# AIO.net
KiCad netlist of a schematic drawn in EAGLE
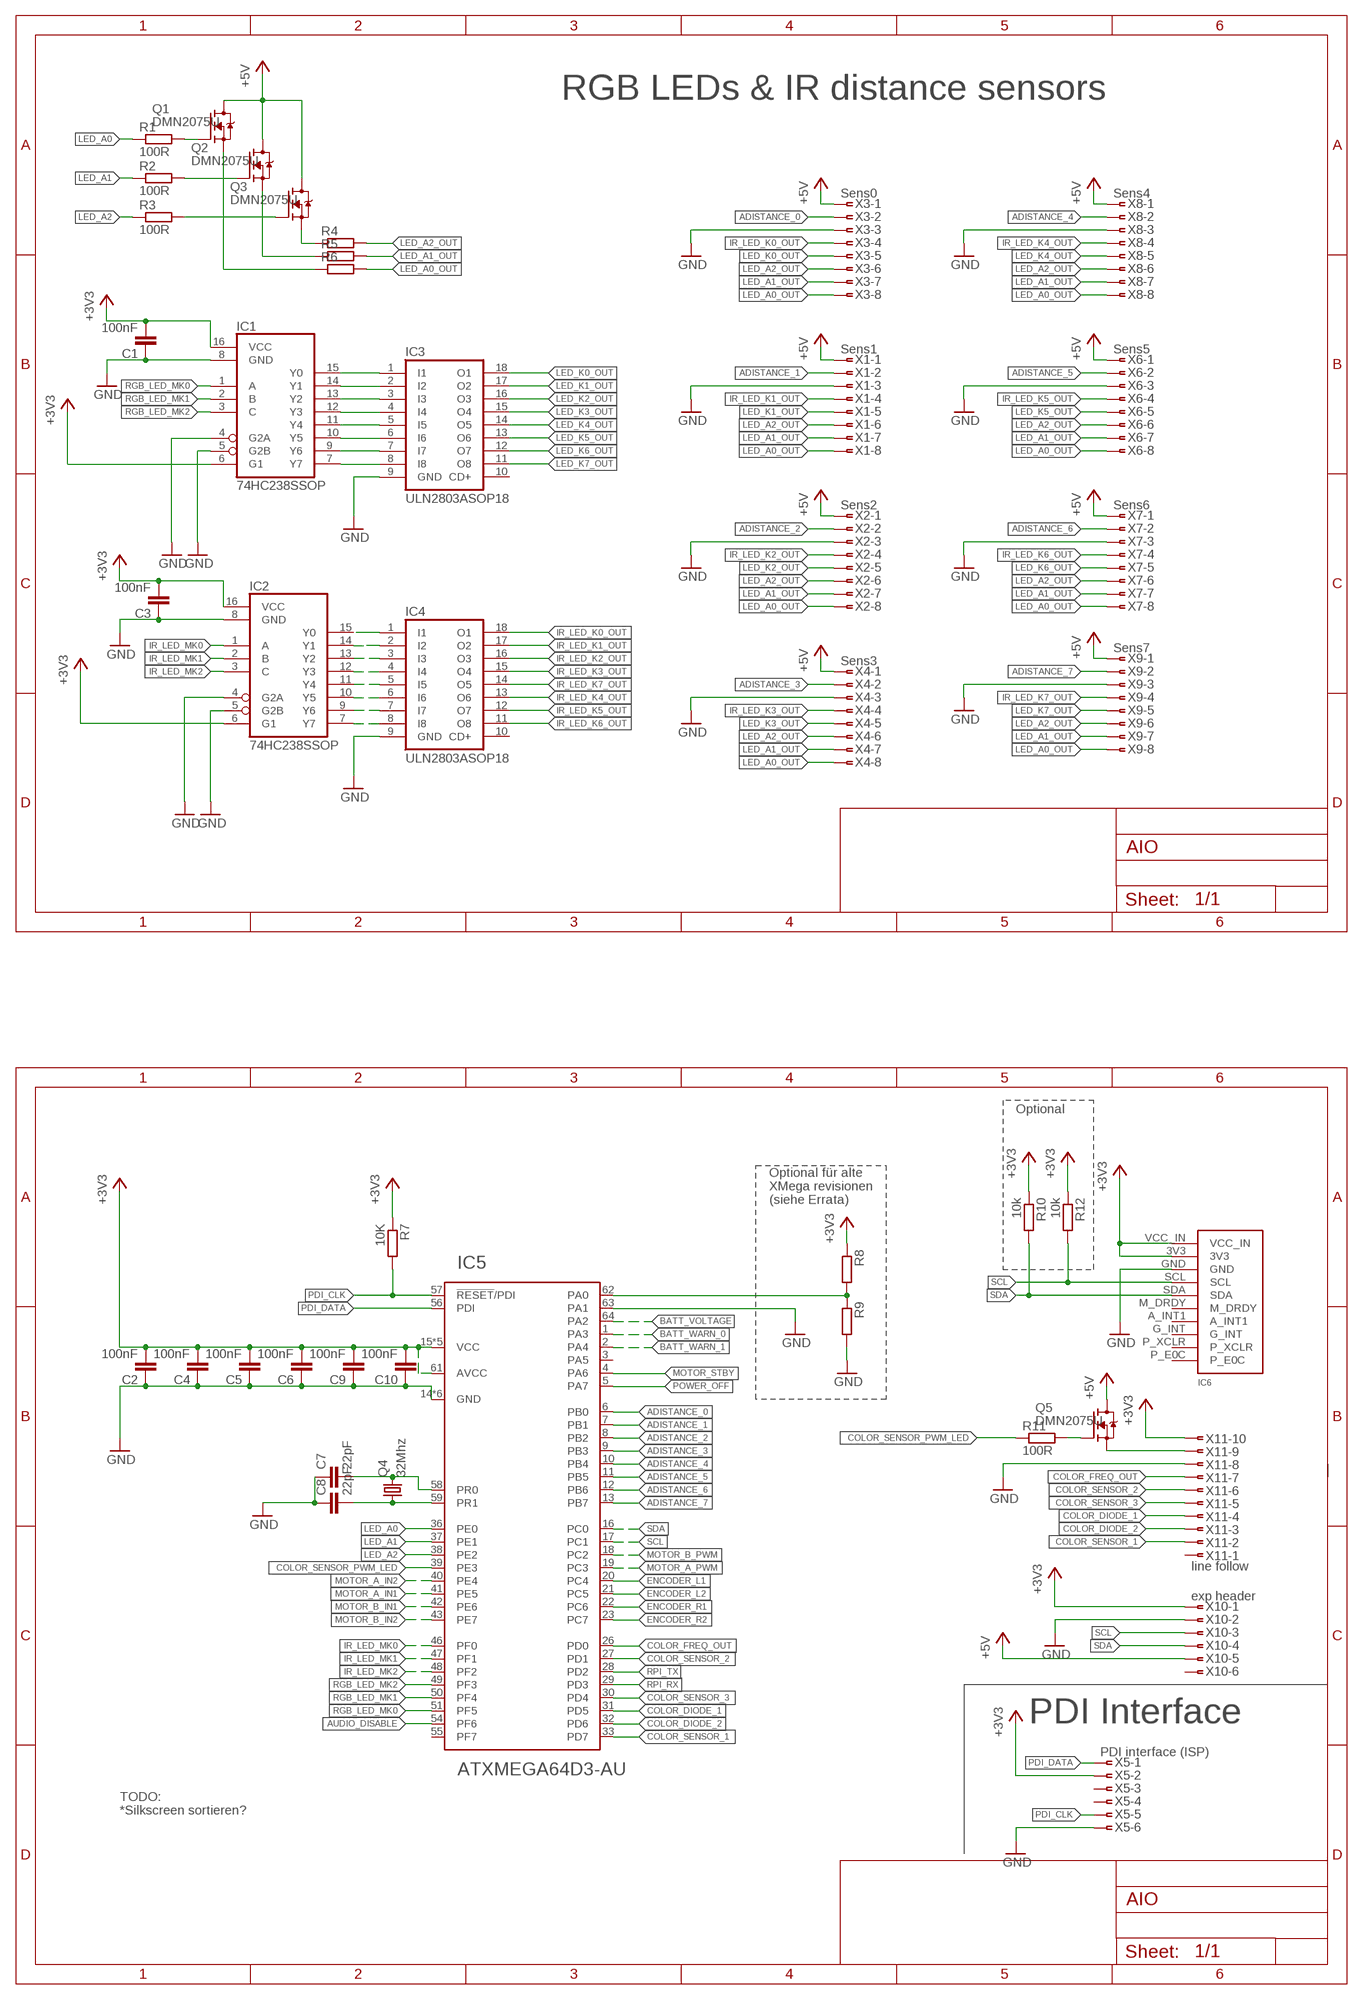
[diagram p0: schematic, sheet 1, part 1 of 2]
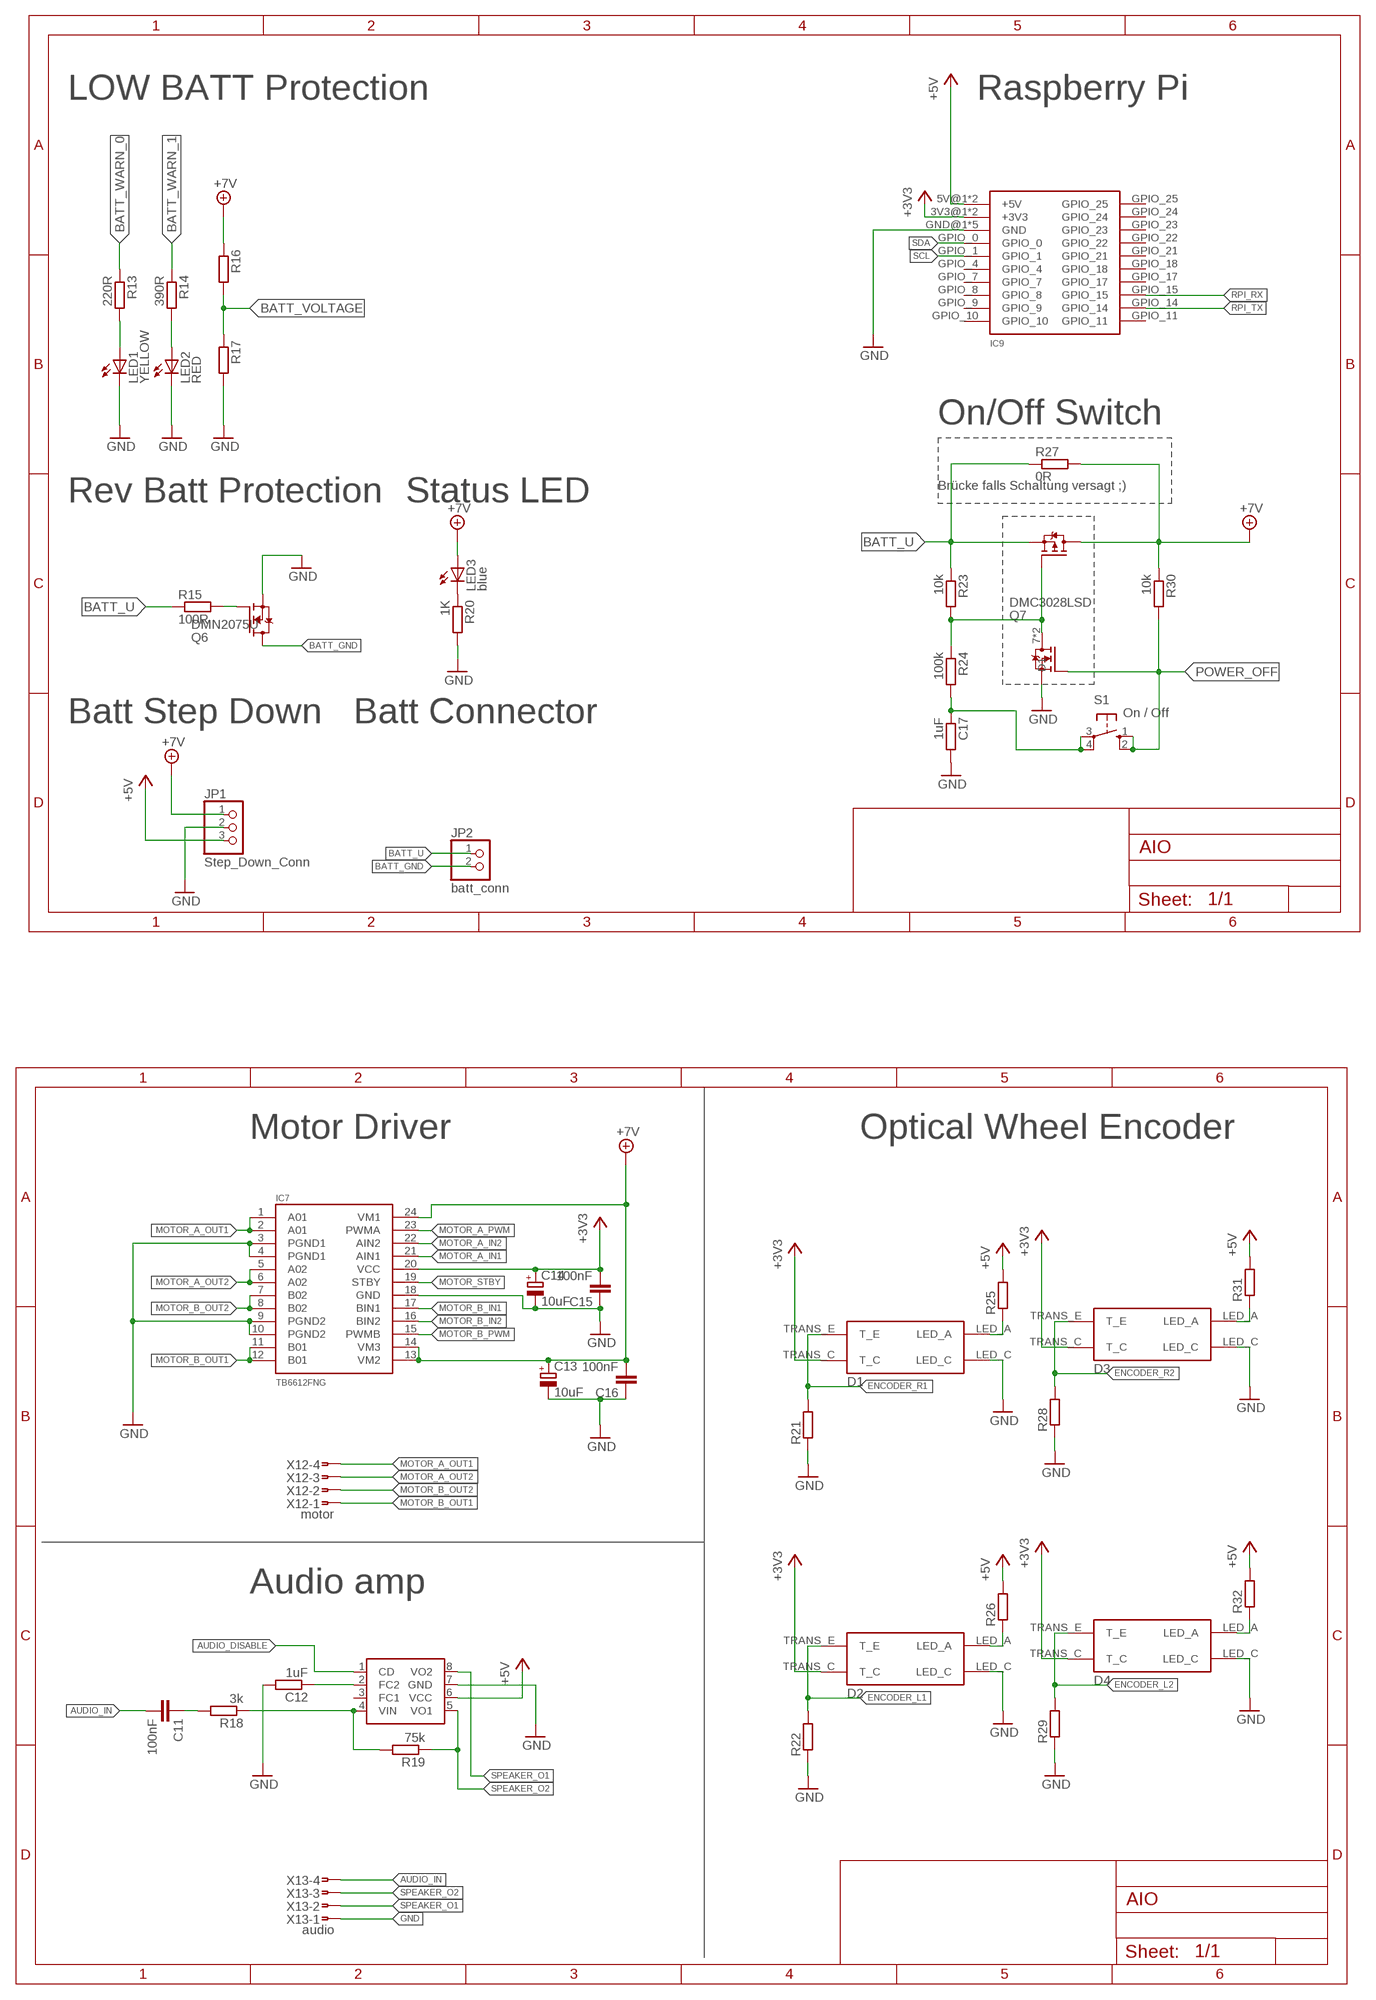
[diagram p1: schematic, sheet 1, part 2 of 2]

(export (version "E")
  (design (tool "Eeschema 10.0.6"))
  (components
    (comp (ref "C1")
      (value "100nF")
      (footprint "eagle-import:C0603")
      (libsource (lib "eagle-import") (part "C-EUC0603"))
    )
    (comp (ref "C2")
      (value "100nF")
      (footprint "eagle-import:C0603")
      (libsource (lib "eagle-import") (part "C-EUC0603"))
    )
    (comp (ref "C3")
      (value "100nF")
      (footprint "eagle-import:C0603")
      (libsource (lib "eagle-import") (part "C-EUC0603"))
    )
    (comp (ref "C4")
      (value "100nF")
      (footprint "eagle-import:C0603")
      (libsource (lib "eagle-import") (part "C-EUC0603"))
    )
    (comp (ref "C5")
      (value "100nF")
      (footprint "eagle-import:C0603")
      (libsource (lib "eagle-import") (part "C-EUC0603"))
    )
    (comp (ref "C6")
      (value "100nF")
      (footprint "eagle-import:C0603")
      (libsource (lib "eagle-import") (part "C-EUC0603"))
    )
    (comp (ref "C7")
      (value "22pF")
      (footprint "eagle-import:C0603")
      (libsource (lib "eagle-import") (part "C-EUC0603"))
    )
    (comp (ref "C8")
      (value "22pF")
      (footprint "eagle-import:C0603")
      (libsource (lib "eagle-import") (part "C-EUC0603"))
    )
    (comp (ref "C9")
      (value "100nF")
      (footprint "eagle-import:C0603")
      (libsource (lib "eagle-import") (part "C-EUC0603"))
    )
    (comp (ref "C10")
      (value "100nF")
      (footprint "eagle-import:C0603")
      (libsource (lib "eagle-import") (part "C-EUC0603"))
    )
    (comp (ref "C11")
      (value "100nF")
      (footprint "eagle-import:C0603")
      (libsource (lib "eagle-import") (part "C-EUC0603"))
    )
    (comp (ref "C12")
      (value "1uF")
      (footprint "eagle-import:M0805")
      (libsource (lib "eagle-import") (part "resistor_R-EU_M0805"))
    )
    (comp (ref "C13")
      (value "10uF")
      (footprint "eagle-import:E2-5")
      (libsource (lib "eagle-import") (part "CPOL-EUE2-5"))
    )
    (comp (ref "C14")
      (value "10uF")
      (footprint "eagle-import:E2-5")
      (libsource (lib "eagle-import") (part "CPOL-EUE2-5"))
    )
    (comp (ref "C15")
      (value "100nF")
      (footprint "eagle-import:C0603")
      (libsource (lib "eagle-import") (part "C-EUC0603"))
    )
    (comp (ref "C16")
      (value "100nF")
      (footprint "eagle-import:C0603")
      (libsource (lib "eagle-import") (part "C-EUC0603"))
    )
    (comp (ref "C17")
      (value "1uF")
      (footprint "eagle-import:M0805")
      (libsource (lib "eagle-import") (part "resistor_R-EU_M0805"))
    )
    (comp (ref "D1")
      (value "CNY70")
      (footprint "eagle-import:CNY70")
      (libsource (lib "eagle-import") (part "CNY70"))
    )
    (comp (ref "D2")
      (value "CNY70")
      (footprint "eagle-import:CNY70")
      (libsource (lib "eagle-import") (part "CNY70"))
    )
    (comp (ref "D3")
      (value "CNY70")
      (footprint "eagle-import:CNY70")
      (libsource (lib "eagle-import") (part "CNY70"))
    )
    (comp (ref "D4")
      (value "CNY70")
      (footprint "eagle-import:CNY70")
      (libsource (lib "eagle-import") (part "CNY70"))
    )
    (comp (ref "IC1")
      (value "74HC238SSOP")
      (footprint "eagle-import:SSOP16")
      (libsource (lib "eagle-import") (part "74HC238SSOP"))
    )
    (comp (ref "IC2")
      (value "74HC238SSOP")
      (footprint "eagle-import:SSOP16")
      (libsource (lib "eagle-import") (part "74HC238SSOP"))
    )
    (comp (ref "IC3")
      (value "ULN2803ASOP18")
      (footprint "eagle-import:SOP18")
      (libsource (lib "eagle-import") (part "ULN2803ASOP18"))
    )
    (comp (ref "IC4")
      (value "ULN2803ASOP18")
      (footprint "eagle-import:SOP18")
      (libsource (lib "eagle-import") (part "ULN2803ASOP18"))
    )
    (comp (ref "IC5")
      (value "ATXMEGA64D3-AU")
      (footprint "eagle-import:TQFP-64A-64")
      (libsource (lib "eagle-import") (part "ATXMEGA64D3-AU"))
    )
    (comp (ref "IC6")
      (value "GY-81")
      (footprint "eagle-import:GY-81")
      (libsource (lib "eagle-import") (part "GY-81"))
    )
    (comp (ref "IC7")
      (value "TB6612FNG")
      (footprint "eagle-import:SSOP24")
      (libsource (lib "eagle-import") (part "TB6621FNG"))
    )
    (comp (ref "IC8")
      (value "TS34119SMD")
      (footprint "eagle-import:SO08")
      (libsource (lib "eagle-import") (part "TS34119SMD"))
    )
    (comp (ref "IC9")
      (value "RASPBERRY-PI")
      (footprint "eagle-import:RASPERRRY-PI")
      (libsource (lib "eagle-import") (part "RASPBERRY-PI"))
    )
    (comp (ref "JP1")
      (value "Step_Down_Conn")
      (footprint "eagle-import:1X03")
      (libsource (lib "eagle-import") (part "PINHD-1X3"))
    )
    (comp (ref "JP2")
      (value "batt_conn")
      (footprint "eagle-import:1X02")
      (libsource (lib "eagle-import") (part "PINHD-1X2"))
    )
    (comp (ref "LED1")
      (value "YELLOW")
      (footprint "eagle-import:CHIPLED_0603")
      (libsource (lib "eagle-import") (part "LEDCHIPLED_0603"))
    )
    (comp (ref "LED2")
      (value "RED")
      (footprint "eagle-import:CHIPLED_0603")
      (libsource (lib "eagle-import") (part "LEDCHIPLED_0603"))
    )
    (comp (ref "LED3")
      (value "blue")
      (footprint "eagle-import:CHIPLED_0603")
      (libsource (lib "eagle-import") (part "LEDCHIPLED_0603"))
    )
    (comp (ref "Q1")
      (value "DMN2075U")
      (footprint "eagle-import:SOT95P240X112-3N")
      (libsource (lib "eagle-import") (part "DMN2075U"))
    )
    (comp (ref "Q2")
      (value "DMN2075U")
      (footprint "eagle-import:SOT95P240X112-3N")
      (libsource (lib "eagle-import") (part "DMN2075U"))
    )
    (comp (ref "Q3")
      (value "DMN2075U")
      (footprint "eagle-import:SOT95P240X112-3N")
      (libsource (lib "eagle-import") (part "DMN2075U"))
    )
    (comp (ref "Q4")
      (value "32Mhz")
      (footprint "eagle-import:HC18U-V")
      (libsource (lib "eagle-import") (part "CRYSTALHC18U-V"))
    )
    (comp (ref "Q5")
      (value "DMN2075U")
      (footprint "eagle-import:SOT95P240X112-3N")
      (libsource (lib "eagle-import") (part "DMN2075U"))
    )
    (comp (ref "Q6")
      (value "DMN2075U")
      (footprint "eagle-import:SOT95P240X112-3N")
      (libsource (lib "eagle-import") (part "DMN2075U"))
    )
    (comp (ref "Q7")
      (value "DMC3028LSD")
      (footprint "eagle-import:SO08")
      (libsource (lib "eagle-import") (part "DMC3028LSD"))
    )
    (comp (ref "R1")
      (value "100R")
      (footprint "eagle-import:R0603")
      (libsource (lib "eagle-import") (part "R-EU_R0603"))
    )
    (comp (ref "R2")
      (value "100R")
      (footprint "eagle-import:R0603")
      (libsource (lib "eagle-import") (part "R-EU_R0603"))
    )
    (comp (ref "R3")
      (value "100R")
      (footprint "eagle-import:R0603")
      (libsource (lib "eagle-import") (part "R-EU_R0603"))
    )
    (comp (ref "R4")
      (value "R-EU_M0805")
      (footprint "eagle-import:M0805")
      (libsource (lib "eagle-import") (part "resistor_R-EU_M0805"))
    )
    (comp (ref "R5")
      (value "R-EU_M0805")
      (footprint "eagle-import:M0805")
      (libsource (lib "eagle-import") (part "resistor_R-EU_M0805"))
    )
    (comp (ref "R6")
      (value "R-EU_M0805")
      (footprint "eagle-import:M0805")
      (libsource (lib "eagle-import") (part "resistor_R-EU_M0805"))
    )
    (comp (ref "R7")
      (value "10K")
      (footprint "eagle-import:M0805")
      (libsource (lib "eagle-import") (part "resistor_R-EU_M0805"))
    )
    (comp (ref "R8")
      (value "R-EU_M0805")
      (footprint "eagle-import:M0805")
      (libsource (lib "eagle-import") (part "R-EU_M0805"))
    )
    (comp (ref "R9")
      (value "R-EU_M0805")
      (footprint "eagle-import:M0805")
      (libsource (lib "eagle-import") (part "R-EU_M0805"))
    )
    (comp (ref "R10")
      (value "10k")
      (footprint "eagle-import:M0805")
      (libsource (lib "eagle-import") (part "resistor_R-EU_M0805"))
    )
    (comp (ref "R11")
      (value "100R")
      (footprint "eagle-import:R0603")
      (libsource (lib "eagle-import") (part "R-EU_R0603"))
    )
    (comp (ref "R12")
      (value "10k")
      (footprint "eagle-import:M0805")
      (libsource (lib "eagle-import") (part "resistor_R-EU_M0805"))
    )
    (comp (ref "R13")
      (value "220R")
      (footprint "eagle-import:M0805")
      (libsource (lib "eagle-import") (part "resistor_R-EU_M0805"))
    )
    (comp (ref "R14")
      (value "390R")
      (footprint "eagle-import:M0805")
      (libsource (lib "eagle-import") (part "resistor_R-EU_M0805"))
    )
    (comp (ref "R15")
      (value "100R")
      (footprint "eagle-import:R0603")
      (libsource (lib "eagle-import") (part "R-EU_R0603"))
    )
    (comp (ref "R16")
      (value "R-EU_M0805")
      (footprint "eagle-import:M0805")
      (libsource (lib "eagle-import") (part "resistor_R-EU_M0805"))
    )
    (comp (ref "R17")
      (value "R-EU_M0805")
      (footprint "eagle-import:M0805")
      (libsource (lib "eagle-import") (part "resistor_R-EU_M0805"))
    )
    (comp (ref "R18")
      (value "3k")
      (footprint "eagle-import:M0805")
      (libsource (lib "eagle-import") (part "resistor_R-EU_M0805"))
    )
    (comp (ref "R19")
      (value "75k")
      (footprint "eagle-import:M0805")
      (libsource (lib "eagle-import") (part "resistor_R-EU_M0805"))
    )
    (comp (ref "R20")
      (value "1K")
      (footprint "eagle-import:M0805")
      (libsource (lib "eagle-import") (part "resistor_R-EU_M0805"))
    )
    (comp (ref "R21")
      (value "R-EU_M0805")
      (footprint "eagle-import:M0805")
      (libsource (lib "eagle-import") (part "resistor_R-EU_M0805"))
    )
    (comp (ref "R22")
      (value "R-EU_M0805")
      (footprint "eagle-import:M0805")
      (libsource (lib "eagle-import") (part "resistor_R-EU_M0805"))
    )
    (comp (ref "R23")
      (value "10k")
      (footprint "eagle-import:M0805")
      (libsource (lib "eagle-import") (part "resistor_R-EU_M0805"))
    )
    (comp (ref "R24")
      (value "100k")
      (footprint "eagle-import:M0805")
      (libsource (lib "eagle-import") (part "resistor_R-EU_M0805"))
    )
    (comp (ref "R25")
      (value "R-EU_M0805")
      (footprint "eagle-import:M0805")
      (libsource (lib "eagle-import") (part "resistor_R-EU_M0805"))
    )
    (comp (ref "R26")
      (value "R-EU_M0805")
      (footprint "eagle-import:M0805")
      (libsource (lib "eagle-import") (part "resistor_R-EU_M0805"))
    )
    (comp (ref "R27")
      (value "0R")
      (footprint "eagle-import:M0805")
      (libsource (lib "eagle-import") (part "resistor_R-EU_M0805"))
    )
    (comp (ref "R28")
      (value "R-EU_M0805")
      (footprint "eagle-import:M0805")
      (libsource (lib "eagle-import") (part "resistor_R-EU_M0805"))
    )
    (comp (ref "R29")
      (value "R-EU_M0805")
      (footprint "eagle-import:M0805")
      (libsource (lib "eagle-import") (part "resistor_R-EU_M0805"))
    )
    (comp (ref "R30")
      (value "10k")
      (footprint "eagle-import:M0805")
      (libsource (lib "eagle-import") (part "resistor_R-EU_M0805"))
    )
    (comp (ref "R31")
      (value "R-EU_M0805")
      (footprint "eagle-import:M0805")
      (libsource (lib "eagle-import") (part "resistor_R-EU_M0805"))
    )
    (comp (ref "R32")
      (value "R-EU_M0805")
      (footprint "eagle-import:M0805")
      (libsource (lib "eagle-import") (part "resistor_R-EU_M0805"))
    )
    (comp (ref "S1")
      (value "On / Off")
      (footprint "eagle-import:B3F-10XX")
      (fields (field (name "MPN") "B3F-1000"))
      (libsource (lib "eagle-import") (part "10-XX"))
    )
    (comp (ref "X1")
      (value "Sens1")
      (footprint "eagle-import:FSIDE-8")
      (libsource (lib "eagle-import") (part "FSIDE-8"))
    )
    (comp (ref "X2")
      (value "Sens2")
      (footprint "eagle-import:FSIDE-8")
      (libsource (lib "eagle-import") (part "FSIDE-8"))
    )
    (comp (ref "X3")
      (value "Sens0")
      (footprint "eagle-import:FTOP-8")
      (libsource (lib "eagle-import") (part "FTOP-8"))
    )
    (comp (ref "X4")
      (value "Sens3")
      (footprint "eagle-import:FTOP-8")
      (libsource (lib "eagle-import") (part "FTOP-8"))
    )
    (comp (ref "X5")
      (value "PDI interface (ISP)")
      (footprint "eagle-import:FTOP-6")
      (libsource (lib "eagle-import") (part "FTOP-6"))
    )
    (comp (ref "X6")
      (value "Sens5")
      (footprint "eagle-import:FSIDE-8")
      (libsource (lib "eagle-import") (part "FSIDE-8"))
    )
    (comp (ref "X7")
      (value "Sens6")
      (footprint "eagle-import:FSIDE-8")
      (libsource (lib "eagle-import") (part "FSIDE-8"))
    )
    (comp (ref "X8")
      (value "Sens4")
      (footprint "eagle-import:FTOP-8")
      (libsource (lib "eagle-import") (part "FTOP-8"))
    )
    (comp (ref "X9")
      (value "Sens7")
      (footprint "eagle-import:FTOP-8")
      (libsource (lib "eagle-import") (part "FTOP-8"))
    )
    (comp (ref "X10")
      (value "exp header")
      (footprint "eagle-import:FTOP-6")
      (libsource (lib "eagle-import") (part "FTOP-6"))
    )
    (comp (ref "X11")
      (value "line follow")
      (footprint "eagle-import:FTOP-10")
      (libsource (lib "eagle-import") (part "FTOP-10"))
    )
    (comp (ref "X12")
      (value "motor")
      (footprint "eagle-import:FTOP-4")
      (libsource (lib "eagle-import") (part "FTOP-4"))
    )
    (comp (ref "X13")
      (value "audio")
      (footprint "eagle-import:FTOP-4")
      (libsource (lib "eagle-import") (part "FTOP-4"))
    )
  )
  (nets
    (net (code "1") (name "+3V3") (class "Default")
      (node (ref "C1") (pin "2") (pinfunction "2_2") (pintype "passive"))
      (node (ref "C10") (pin "2") (pinfunction "2_2") (pintype "passive"))
      (node (ref "C14") (pin "+") (pinfunction "+_+") (pintype "passive"))
      (node (ref "C15") (pin "2") (pinfunction "2_2") (pintype "passive"))
      (node (ref "C2") (pin "2") (pinfunction "2_2") (pintype "passive"))
      (node (ref "C3") (pin "2") (pinfunction "2_2") (pintype "passive"))
      (node (ref "C4") (pin "2") (pinfunction "2_2") (pintype "passive"))
      (node (ref "C5") (pin "2") (pinfunction "2_2") (pintype "passive"))
      (node (ref "C6") (pin "2") (pinfunction "2_2") (pintype "passive"))
      (node (ref "C9") (pin "2") (pinfunction "2_2") (pintype "passive"))
      (node (ref "D1") (pin "TRANS_C") (pinfunction "T_C_TRANS_C") (pintype "bidirectional"))
      (node (ref "D2") (pin "TRANS_C") (pinfunction "T_C_TRANS_C") (pintype "bidirectional"))
      (node (ref "D3") (pin "TRANS_C") (pinfunction "T_C_TRANS_C") (pintype "bidirectional"))
      (node (ref "D4") (pin "TRANS_C") (pinfunction "T_C_TRANS_C") (pintype "bidirectional"))
      (node (ref "IC1") (pin "16") (pinfunction "VCC_16") (pintype "power_in"))
      (node (ref "IC1") (pin "6") (pinfunction "G1_6") (pintype "input"))
      (node (ref "IC2") (pin "16") (pinfunction "VCC_16") (pintype "power_in"))
      (node (ref "IC2") (pin "6") (pinfunction "G1_6") (pintype "input"))
      (node (ref "IC5") (pin "15") (pinfunction "VCC_15") (pintype "power_in"))
      (node (ref "IC5") (pin "25") (pinfunction "VCC_25") (pintype "power_in"))
      (node (ref "IC5") (pin "35") (pinfunction "VCC_35") (pintype "power_in"))
      (node (ref "IC5") (pin "45") (pinfunction "VCC_45") (pintype "power_in"))
      (node (ref "IC5") (pin "53") (pinfunction "VCC_53") (pintype "power_in"))
      (node (ref "IC5") (pin "61") (pinfunction "AVCC_61") (pintype "power_in"))
      (node (ref "IC6") (pin "3V3") (pinfunction "3V3_3V3") (pintype "bidirectional"))
      (node (ref "IC6") (pin "VCC_IN") (pinfunction "VCC_IN_VCC_IN") (pintype "bidirectional"))
      (node (ref "IC7") (pin "20") (pinfunction "VCC_20") (pintype "bidirectional"))
      (node (ref "IC9") (pin "3V3@1") (pinfunction "+3V3_3V3@1") (pintype "power_in"))
      (node (ref "IC9") (pin "3V3@2") (pinfunction "+3V3_3V3@2") (pintype "power_in"))
      (node (ref "R10") (pin "1") (pinfunction "1_1") (pintype "passive"))
      (node (ref "R12") (pin "1") (pinfunction "1_1") (pintype "passive"))
      (node (ref "R7") (pin "1") (pinfunction "1_1") (pintype "passive"))
      (node (ref "R8") (pin "1") (pinfunction "1_1") (pintype "passive"))
      (node (ref "X10") (pin "1") (pinfunction "1_1") (pintype "passive"))
      (node (ref "X11") (pin "10") (pinfunction "1_10") (pintype "passive"))
      (node (ref "X5") (pin "2") (pinfunction "1_2") (pintype "passive"))
    )
    (net (code "2") (name "+5V") (class "Default")
      (node (ref "IC8") (pin "6") (pinfunction "VCC_6") (pintype "bidirectional"))
      (node (ref "IC9") (pin "5V@1") (pinfunction "+5V_5V@1") (pintype "power_in"))
      (node (ref "IC9") (pin "5V@2") (pinfunction "+5V_5V@2") (pintype "power_in"))
      (node (ref "JP1") (pin "3") (pinfunction "3_3") (pintype "passive"))
      (node (ref "Q1") (pin "D") (pinfunction "D_D") (pintype "passive"))
      (node (ref "Q2") (pin "D") (pinfunction "D_D") (pintype "passive"))
      (node (ref "Q3") (pin "D") (pinfunction "D_D") (pintype "passive"))
      (node (ref "Q5") (pin "D") (pinfunction "D_D") (pintype "passive"))
      (node (ref "R25") (pin "2") (pinfunction "2_2") (pintype "passive"))
      (node (ref "R26") (pin "2") (pinfunction "2_2") (pintype "passive"))
      (node (ref "R31") (pin "2") (pinfunction "2_2") (pintype "passive"))
      (node (ref "R32") (pin "2") (pinfunction "2_2") (pintype "passive"))
      (node (ref "X1") (pin "1") (pinfunction "1_1") (pintype "passive"))
      (node (ref "X10") (pin "5") (pinfunction "1_5") (pintype "passive"))
      (node (ref "X2") (pin "1") (pinfunction "1_1") (pintype "passive"))
      (node (ref "X3") (pin "1") (pinfunction "1_1") (pintype "passive"))
      (node (ref "X4") (pin "1") (pinfunction "1_1") (pintype "passive"))
      (node (ref "X6") (pin "1") (pinfunction "1_1") (pintype "passive"))
      (node (ref "X7") (pin "1") (pinfunction "1_1") (pintype "passive"))
      (node (ref "X8") (pin "1") (pinfunction "1_1") (pintype "passive"))
      (node (ref "X9") (pin "1") (pinfunction "1_1") (pintype "passive"))
    )
    (net (code "3") (name "+7V") (class "Default")
      (node (ref "C13") (pin "+") (pinfunction "+_+") (pintype "passive"))
      (node (ref "C16") (pin "2") (pinfunction "2_2") (pintype "passive"))
      (node (ref "IC7") (pin "13") (pinfunction "VM2_13") (pintype "bidirectional"))
      (node (ref "IC7") (pin "14") (pinfunction "VM3_14") (pintype "bidirectional"))
      (node (ref "IC7") (pin "24") (pinfunction "VM1_24") (pintype "bidirectional"))
      (node (ref "JP1") (pin "1") (pinfunction "1_1") (pintype "passive"))
      (node (ref "LED3") (pin "A") (pinfunction "A_A") (pintype "passive"))
      (node (ref "Q7") (pin "5") (pinfunction "D2_5") (pintype "passive"))
      (node (ref "Q7") (pin "6") (pinfunction "D2_6") (pintype "passive"))
      (node (ref "R16") (pin "1") (pinfunction "1_1") (pintype "passive"))
      (node (ref "R27") (pin "2") (pinfunction "2_2") (pintype "passive"))
      (node (ref "R30") (pin "1") (pinfunction "1_1") (pintype "passive"))
    )
    (net (code "4") (name "ADISTANCE_0") (class "Default")
      (node (ref "IC5") (pin "6") (pinfunction "PB0_6") (pintype "bidirectional"))
      (node (ref "X3") (pin "2") (pinfunction "1_2") (pintype "passive"))
    )
    (net (code "5") (name "ADISTANCE_1") (class "Default")
      (node (ref "IC5") (pin "7") (pinfunction "PB1_7") (pintype "bidirectional"))
      (node (ref "X1") (pin "2") (pinfunction "1_2") (pintype "passive"))
    )
    (net (code "6") (name "ADISTANCE_2") (class "Default")
      (node (ref "IC5") (pin "8") (pinfunction "PB2_8") (pintype "bidirectional"))
      (node (ref "X2") (pin "2") (pinfunction "1_2") (pintype "passive"))
    )
    (net (code "7") (name "ADISTANCE_3") (class "Default")
      (node (ref "IC5") (pin "9") (pinfunction "PB3_9") (pintype "bidirectional"))
      (node (ref "X4") (pin "2") (pinfunction "1_2") (pintype "passive"))
    )
    (net (code "8") (name "ADISTANCE_4") (class "Default")
      (node (ref "IC5") (pin "10") (pinfunction "PB4_10") (pintype "bidirectional"))
      (node (ref "X8") (pin "2") (pinfunction "1_2") (pintype "passive"))
    )
    (net (code "9") (name "ADISTANCE_5") (class "Default")
      (node (ref "IC5") (pin "11") (pinfunction "PB5_11") (pintype "bidirectional"))
      (node (ref "X6") (pin "2") (pinfunction "1_2") (pintype "passive"))
    )
    (net (code "10") (name "ADISTANCE_6") (class "Default")
      (node (ref "IC5") (pin "12") (pinfunction "PB6_12") (pintype "bidirectional"))
      (node (ref "X7") (pin "2") (pinfunction "1_2") (pintype "passive"))
    )
    (net (code "11") (name "ADISTANCE_7") (class "Default")
      (node (ref "IC5") (pin "13") (pinfunction "PB7_13") (pintype "bidirectional"))
      (node (ref "X9") (pin "2") (pinfunction "1_2") (pintype "passive"))
    )
    (net (code "12") (name "AUDIO_DISABLE") (class "Default")
      (node (ref "IC5") (pin "54") (pinfunction "PF6_54") (pintype "bidirectional"))
      (node (ref "IC8") (pin "1") (pinfunction "CD_1") (pintype "bidirectional"))
    )
    (net (code "13") (name "AUDIO_IN") (class "Default")
      (node (ref "C11") (pin "2") (pinfunction "2_2") (pintype "passive"))
      (node (ref "X13") (pin "4") (pinfunction "1_4") (pintype "passive"))
    )
    (net (code "14") (name "BATT_GND") (class "Default")
      (node (ref "JP2") (pin "2") (pinfunction "2_2") (pintype "passive"))
      (node (ref "Q6") (pin "D") (pinfunction "D_D") (pintype "passive"))
    )
    (net (code "15") (name "BATT_U") (class "Default")
      (node (ref "JP2") (pin "1") (pinfunction "1_1") (pintype "passive"))
      (node (ref "Q7") (pin "3") (pinfunction "S2_3") (pintype "passive"))
      (node (ref "R15") (pin "1") (pinfunction "1_1") (pintype "passive"))
      (node (ref "R23") (pin "1") (pinfunction "1_1") (pintype "passive"))
      (node (ref "R27") (pin "1") (pinfunction "1_1") (pintype "passive"))
    )
    (net (code "16") (name "BATT_VOLTAGE") (class "Default")
      (node (ref "IC5") (pin "64") (pinfunction "PA2_64") (pintype "bidirectional"))
      (node (ref "R16") (pin "2") (pinfunction "2_2") (pintype "passive"))
      (node (ref "R17") (pin "1") (pinfunction "1_1") (pintype "passive"))
    )
    (net (code "17") (name "BATT_WARN_0") (class "Default")
      (node (ref "IC5") (pin "1") (pinfunction "PA3_1") (pintype "bidirectional"))
      (node (ref "R13") (pin "1") (pinfunction "1_1") (pintype "passive"))
    )
    (net (code "18") (name "BATT_WARN_1") (class "Default")
      (node (ref "IC5") (pin "2") (pinfunction "PA4_2") (pintype "bidirectional"))
      (node (ref "R14") (pin "1") (pinfunction "1_1") (pintype "passive"))
    )
    (net (code "19") (name "COLOR_DIODE_1") (class "Default")
      (node (ref "IC5") (pin "31") (pinfunction "PD5_31") (pintype "bidirectional"))
      (node (ref "X11") (pin "4") (pinfunction "1_4") (pintype "passive"))
    )
    (net (code "20") (name "COLOR_DIODE_2") (class "Default")
      (node (ref "IC5") (pin "32") (pinfunction "PD6_32") (pintype "bidirectional"))
      (node (ref "X11") (pin "3") (pinfunction "1_3") (pintype "passive"))
    )
    (net (code "21") (name "COLOR_FREQ_OUT") (class "Default")
      (node (ref "IC5") (pin "26") (pinfunction "PD0_26") (pintype "bidirectional"))
      (node (ref "X11") (pin "7") (pinfunction "1_7") (pintype "passive"))
    )
    (net (code "22") (name "COLOR_SENSOR_1") (class "Default")
      (node (ref "IC5") (pin "33") (pinfunction "PD7_33") (pintype "bidirectional"))
      (node (ref "X11") (pin "2") (pinfunction "1_2") (pintype "passive"))
    )
    (net (code "23") (name "COLOR_SENSOR_2") (class "Default")
      (node (ref "IC5") (pin "27") (pinfunction "PD1_27") (pintype "bidirectional"))
      (node (ref "X11") (pin "6") (pinfunction "1_6") (pintype "passive"))
    )
    (net (code "24") (name "COLOR_SENSOR_3") (class "Default")
      (node (ref "IC5") (pin "30") (pinfunction "PD4_30") (pintype "bidirectional"))
      (node (ref "X11") (pin "5") (pinfunction "1_5") (pintype "passive"))
    )
    (net (code "25") (name "COLOR_SENSOR_PWM_LED") (class "Default")
      (node (ref "IC5") (pin "39") (pinfunction "PE3_39") (pintype "bidirectional"))
      (node (ref "R11") (pin "1") (pinfunction "1_1") (pintype "passive"))
    )
    (net (code "26") (name "ENCODER_L1") (class "Default")
      (node (ref "D2") (pin "TRANS_E") (pinfunction "T_E_TRANS_E") (pintype "bidirectional"))
      (node (ref "IC5") (pin "20") (pinfunction "PC4_20") (pintype "bidirectional"))
      (node (ref "R22") (pin "2") (pinfunction "2_2") (pintype "passive"))
    )
    (net (code "27") (name "ENCODER_L2") (class "Default")
      (node (ref "D4") (pin "TRANS_E") (pinfunction "T_E_TRANS_E") (pintype "bidirectional"))
      (node (ref "IC5") (pin "21") (pinfunction "PC5_21") (pintype "bidirectional"))
      (node (ref "R29") (pin "2") (pinfunction "2_2") (pintype "passive"))
    )
    (net (code "28") (name "ENCODER_R1") (class "Default")
      (node (ref "D1") (pin "TRANS_E") (pinfunction "T_E_TRANS_E") (pintype "bidirectional"))
      (node (ref "IC5") (pin "22") (pinfunction "PC6_22") (pintype "bidirectional"))
      (node (ref "R21") (pin "2") (pinfunction "2_2") (pintype "passive"))
    )
    (net (code "29") (name "ENCODER_R2") (class "Default")
      (node (ref "D3") (pin "TRANS_E") (pinfunction "T_E_TRANS_E") (pintype "bidirectional"))
      (node (ref "IC5") (pin "23") (pinfunction "PC7_23") (pintype "bidirectional"))
      (node (ref "R28") (pin "2") (pinfunction "2_2") (pintype "passive"))
    )
    (net (code "30") (name "GND") (class "Default")
      (node (ref "C1") (pin "1") (pinfunction "1_1") (pintype "passive"))
      (node (ref "C10") (pin "1") (pinfunction "1_1") (pintype "passive"))
      (node (ref "C12") (pin "2") (pinfunction "2_2") (pintype "passive"))
      (node (ref "C13") (pin "-") (pinfunction "-_-") (pintype "passive"))
      (node (ref "C14") (pin "-") (pinfunction "-_-") (pintype "passive"))
      (node (ref "C15") (pin "1") (pinfunction "1_1") (pintype "passive"))
      (node (ref "C16") (pin "1") (pinfunction "1_1") (pintype "passive"))
      (node (ref "C17") (pin "2") (pinfunction "2_2") (pintype "passive"))
      (node (ref "C2") (pin "1") (pinfunction "1_1") (pintype "passive"))
      (node (ref "C3") (pin "1") (pinfunction "1_1") (pintype "passive"))
      (node (ref "C4") (pin "1") (pinfunction "1_1") (pintype "passive"))
      (node (ref "C5") (pin "1") (pinfunction "1_1") (pintype "passive"))
      (node (ref "C6") (pin "1") (pinfunction "1_1") (pintype "passive"))
      (node (ref "C7") (pin "1") (pinfunction "1_1") (pintype "passive"))
      (node (ref "C8") (pin "1") (pinfunction "1_1") (pintype "passive"))
      (node (ref "C9") (pin "1") (pinfunction "1_1") (pintype "passive"))
      (node (ref "D1") (pin "LED_C") (pinfunction "LED_C_LED_C") (pintype "bidirectional"))
      (node (ref "D2") (pin "LED_C") (pinfunction "LED_C_LED_C") (pintype "bidirectional"))
      (node (ref "D3") (pin "LED_C") (pinfunction "LED_C_LED_C") (pintype "bidirectional"))
      (node (ref "D4") (pin "LED_C") (pinfunction "LED_C_LED_C") (pintype "bidirectional"))
      (node (ref "IC1") (pin "4") (pinfunction "G2A_4") (pintype "input"))
      (node (ref "IC1") (pin "5") (pinfunction "G2B_5") (pintype "input"))
      (node (ref "IC1") (pin "8") (pinfunction "GND_8") (pintype "power_in"))
      (node (ref "IC2") (pin "4") (pinfunction "G2A_4") (pintype "input"))
      (node (ref "IC2") (pin "5") (pinfunction "G2B_5") (pintype "input"))
      (node (ref "IC2") (pin "8") (pinfunction "GND_8") (pintype "power_in"))
      (node (ref "IC3") (pin "9") (pinfunction "GND_9") (pintype "power_in"))
      (node (ref "IC4") (pin "9") (pinfunction "GND_9") (pintype "power_in"))
      (node (ref "IC5") (pin "14") (pinfunction "GND_14") (pintype "power_in"))
      (node (ref "IC5") (pin "24") (pinfunction "GND_24") (pintype "power_in"))
      (node (ref "IC5") (pin "34") (pinfunction "GND_34") (pintype "power_in"))
      (node (ref "IC5") (pin "44") (pinfunction "GND_44") (pintype "power_in"))
      (node (ref "IC5") (pin "52") (pinfunction "GND_52") (pintype "power_in"))
      (node (ref "IC5") (pin "60") (pinfunction "GND_60") (pintype "power_in"))
      (node (ref "IC5") (pin "63") (pinfunction "PA1_63") (pintype "bidirectional"))
      (node (ref "IC6") (pin "GND") (pinfunction "GND_GND") (pintype "bidirectional"))
      (node (ref "IC7") (pin "10") (pinfunction "PGND2_10") (pintype "bidirectional"))
      (node (ref "IC7") (pin "18") (pinfunction "GND_18") (pintype "bidirectional"))
      (node (ref "IC7") (pin "3") (pinfunction "PGND1_3") (pintype "bidirectional"))
      (node (ref "IC7") (pin "4") (pinfunction "PGND1_4") (pintype "bidirectional"))
      (node (ref "IC7") (pin "9") (pinfunction "PGND2_9") (pintype "bidirectional"))
      (node (ref "IC8") (pin "7") (pinfunction "GND_7") (pintype "bidirectional"))
      (node (ref "IC9") (pin "GND@1") (pinfunction "GND_GND@1") (pintype "power_in"))
      (node (ref "IC9") (pin "GND@2") (pinfunction "GND_GND@2") (pintype "power_in"))
      (node (ref "IC9") (pin "GND@3") (pinfunction "GND_GND@3") (pintype "power_in"))
      (node (ref "IC9") (pin "GND@4") (pinfunction "GND_GND@4") (pintype "power_in"))
      (node (ref "IC9") (pin "GND@5") (pinfunction "GND_GND@5") (pintype "power_in"))
      (node (ref "JP1") (pin "2") (pinfunction "2_2") (pintype "passive"))
      (node (ref "LED1") (pin "C") (pinfunction "C_C") (pintype "passive"))
      (node (ref "LED2") (pin "C") (pinfunction "C_C") (pintype "passive"))
      (node (ref "Q6") (pin "S") (pinfunction "S_S") (pintype "passive"))
      (node (ref "Q7") (pin "1") (pinfunction "S1_1") (pintype "passive"))
      (node (ref "R17") (pin "2") (pinfunction "2_2") (pintype "passive"))
      (node (ref "R20") (pin "2") (pinfunction "2_2") (pintype "passive"))
      (node (ref "R21") (pin "1") (pinfunction "1_1") (pintype "passive"))
      (node (ref "R22") (pin "1") (pinfunction "1_1") (pintype "passive"))
      (node (ref "R28") (pin "1") (pinfunction "1_1") (pintype "passive"))
      (node (ref "R29") (pin "1") (pinfunction "1_1") (pintype "passive"))
      (node (ref "R9") (pin "2") (pinfunction "2_2") (pintype "passive"))
      (node (ref "X1") (pin "3") (pinfunction "1_3") (pintype "passive"))
      (node (ref "X10") (pin "2") (pinfunction "1_2") (pintype "passive"))
      (node (ref "X11") (pin "8") (pinfunction "1_8") (pintype "passive"))
      (node (ref "X13") (pin "1") (pinfunction "1_1") (pintype "passive"))
      (node (ref "X2") (pin "3") (pinfunction "1_3") (pintype "passive"))
      (node (ref "X3") (pin "3") (pinfunction "1_3") (pintype "passive"))
      (node (ref "X4") (pin "3") (pinfunction "1_3") (pintype "passive"))
      (node (ref "X5") (pin "6") (pinfunction "1_6") (pintype "passive"))
      (node (ref "X6") (pin "3") (pinfunction "1_3") (pintype "passive"))
      (node (ref "X7") (pin "3") (pinfunction "1_3") (pintype "passive"))
      (node (ref "X8") (pin "3") (pinfunction "1_3") (pintype "passive"))
      (node (ref "X9") (pin "3") (pinfunction "1_3") (pintype "passive"))
    )
    (net (code "31") (name "IR_LED_K0_OUT") (class "Default")
      (node (ref "IC4") (pin "18") (pinfunction "O1_18") (pintype "open_collector"))
      (node (ref "X3") (pin "4") (pinfunction "1_4") (pintype "passive"))
    )
    (net (code "32") (name "IR_LED_K1_OUT") (class "Default")
      (node (ref "IC4") (pin "17") (pinfunction "O2_17") (pintype "open_collector"))
      (node (ref "X1") (pin "4") (pinfunction "1_4") (pintype "passive"))
    )
    (net (code "33") (name "IR_LED_K2_OUT") (class "Default")
      (node (ref "IC4") (pin "16") (pinfunction "O3_16") (pintype "open_collector"))
      (node (ref "X2") (pin "4") (pinfunction "1_4") (pintype "passive"))
    )
    (net (code "34") (name "IR_LED_K3_OUT") (class "Default")
      (node (ref "IC4") (pin "15") (pinfunction "O4_15") (pintype "open_collector"))
      (node (ref "X4") (pin "4") (pinfunction "1_4") (pintype "passive"))
    )
    (net (code "35") (name "IR_LED_K4_OUT") (class "Default")
      (node (ref "IC4") (pin "13") (pinfunction "O6_13") (pintype "open_collector"))
      (node (ref "X8") (pin "4") (pinfunction "1_4") (pintype "passive"))
    )
    (net (code "36") (name "IR_LED_K5_OUT") (class "Default")
      (node (ref "IC4") (pin "12") (pinfunction "O7_12") (pintype "open_collector"))
      (node (ref "X6") (pin "4") (pinfunction "1_4") (pintype "passive"))
    )
    (net (code "37") (name "IR_LED_K6_OUT") (class "Default")
      (node (ref "IC4") (pin "11") (pinfunction "O8_11") (pintype "open_collector"))
      (node (ref "X7") (pin "4") (pinfunction "1_4") (pintype "passive"))
    )
    (net (code "38") (name "IR_LED_K7_OUT") (class "Default")
      (node (ref "IC4") (pin "14") (pinfunction "O5_14") (pintype "open_collector"))
      (node (ref "X9") (pin "4") (pinfunction "1_4") (pintype "passive"))
    )
    (net (code "39") (name "IR_LED_MK0") (class "Default")
      (node (ref "IC2") (pin "1") (pinfunction "A_1") (pintype "input"))
      (node (ref "IC5") (pin "46") (pinfunction "PF0_46") (pintype "bidirectional"))
    )
    (net (code "40") (name "IR_LED_MK1") (class "Default")
      (node (ref "IC2") (pin "2") (pinfunction "B_2") (pintype "input"))
      (node (ref "IC5") (pin "47") (pinfunction "PF1_47") (pintype "bidirectional"))
    )
    (net (code "41") (name "IR_LED_MK2") (class "Default")
      (node (ref "IC2") (pin "3") (pinfunction "C_3") (pintype "input"))
      (node (ref "IC5") (pin "48") (pinfunction "PF2_48") (pintype "bidirectional"))
    )
    (net (code "42") (name "LED_A0") (class "Default")
      (node (ref "IC5") (pin "36") (pinfunction "PE0_36") (pintype "bidirectional"))
      (node (ref "R1") (pin "1") (pinfunction "1_1") (pintype "passive"))
    )
    (net (code "43") (name "LED_A0_OUT") (class "Default")
      (node (ref "R6") (pin "2") (pinfunction "2_2") (pintype "passive"))
      (node (ref "X1") (pin "8") (pinfunction "1_8") (pintype "passive"))
      (node (ref "X2") (pin "8") (pinfunction "1_8") (pintype "passive"))
      (node (ref "X3") (pin "8") (pinfunction "1_8") (pintype "passive"))
      (node (ref "X4") (pin "8") (pinfunction "1_8") (pintype "passive"))
      (node (ref "X6") (pin "8") (pinfunction "1_8") (pintype "passive"))
      (node (ref "X7") (pin "8") (pinfunction "1_8") (pintype "passive"))
      (node (ref "X8") (pin "8") (pinfunction "1_8") (pintype "passive"))
      (node (ref "X9") (pin "8") (pinfunction "1_8") (pintype "passive"))
    )
    (net (code "44") (name "LED_A1") (class "Default")
      (node (ref "IC5") (pin "37") (pinfunction "PE1_37") (pintype "bidirectional"))
      (node (ref "R2") (pin "1") (pinfunction "1_1") (pintype "passive"))
    )
    (net (code "45") (name "LED_A1_OUT") (class "Default")
      (node (ref "R5") (pin "2") (pinfunction "2_2") (pintype "passive"))
      (node (ref "X1") (pin "7") (pinfunction "1_7") (pintype "passive"))
      (node (ref "X2") (pin "7") (pinfunction "1_7") (pintype "passive"))
      (node (ref "X3") (pin "7") (pinfunction "1_7") (pintype "passive"))
      (node (ref "X4") (pin "7") (pinfunction "1_7") (pintype "passive"))
      (node (ref "X6") (pin "7") (pinfunction "1_7") (pintype "passive"))
      (node (ref "X7") (pin "7") (pinfunction "1_7") (pintype "passive"))
      (node (ref "X8") (pin "7") (pinfunction "1_7") (pintype "passive"))
      (node (ref "X9") (pin "7") (pinfunction "1_7") (pintype "passive"))
    )
    (net (code "46") (name "LED_A2") (class "Default")
      (node (ref "IC5") (pin "38") (pinfunction "PE2_38") (pintype "bidirectional"))
      (node (ref "R3") (pin "1") (pinfunction "1_1") (pintype "passive"))
    )
    (net (code "47") (name "LED_A2_OUT") (class "Default")
      (node (ref "R4") (pin "2") (pinfunction "2_2") (pintype "passive"))
      (node (ref "X1") (pin "6") (pinfunction "1_6") (pintype "passive"))
      (node (ref "X2") (pin "6") (pinfunction "1_6") (pintype "passive"))
      (node (ref "X3") (pin "6") (pinfunction "1_6") (pintype "passive"))
      (node (ref "X4") (pin "6") (pinfunction "1_6") (pintype "passive"))
      (node (ref "X6") (pin "6") (pinfunction "1_6") (pintype "passive"))
      (node (ref "X7") (pin "6") (pinfunction "1_6") (pintype "passive"))
      (node (ref "X8") (pin "6") (pinfunction "1_6") (pintype "passive"))
      (node (ref "X9") (pin "6") (pinfunction "1_6") (pintype "passive"))
    )
    (net (code "48") (name "LED_K0_OUT") (class "Default")
      (node (ref "IC3") (pin "18") (pinfunction "O1_18") (pintype "open_collector"))
      (node (ref "X3") (pin "5") (pinfunction "1_5") (pintype "passive"))
    )
    (net (code "49") (name "LED_K1_OUT") (class "Default")
      (node (ref "IC3") (pin "17") (pinfunction "O2_17") (pintype "open_collector"))
      (node (ref "X1") (pin "5") (pinfunction "1_5") (pintype "passive"))
    )
    (net (code "50") (name "LED_K2_OUT") (class "Default")
      (node (ref "IC3") (pin "16") (pinfunction "O3_16") (pintype "open_collector"))
      (node (ref "X2") (pin "5") (pinfunction "1_5") (pintype "passive"))
    )
    (net (code "51") (name "LED_K3_OUT") (class "Default")
      (node (ref "IC3") (pin "15") (pinfunction "O4_15") (pintype "open_collector"))
      (node (ref "X4") (pin "5") (pinfunction "1_5") (pintype "passive"))
    )
    (net (code "52") (name "LED_K4_OUT") (class "Default")
      (node (ref "IC3") (pin "14") (pinfunction "O5_14") (pintype "open_collector"))
      (node (ref "X8") (pin "5") (pinfunction "1_5") (pintype "passive"))
    )
    (net (code "53") (name "LED_K5_OUT") (class "Default")
      (node (ref "IC3") (pin "13") (pinfunction "O6_13") (pintype "open_collector"))
      (node (ref "X6") (pin "5") (pinfunction "1_5") (pintype "passive"))
    )
    (net (code "54") (name "LED_K6_OUT") (class "Default")
      (node (ref "IC3") (pin "12") (pinfunction "O7_12") (pintype "open_collector"))
      (node (ref "X7") (pin "5") (pinfunction "1_5") (pintype "passive"))
    )
    (net (code "55") (name "LED_K7_OUT") (class "Default")
      (node (ref "IC3") (pin "11") (pinfunction "O8_11") (pintype "open_collector"))
      (node (ref "X9") (pin "5") (pinfunction "1_5") (pintype "passive"))
    )
    (net (code "56") (name "MOTOR_A_IN1") (class "Default")
      (node (ref "IC5") (pin "41") (pinfunction "PE5_41") (pintype "bidirectional"))
      (node (ref "IC7") (pin "21") (pinfunction "AIN1_21") (pintype "bidirectional"))
    )
    (net (code "57") (name "MOTOR_A_IN2") (class "Default")
      (node (ref "IC5") (pin "40") (pinfunction "PE4_40") (pintype "bidirectional"))
      (node (ref "IC7") (pin "22") (pinfunction "AIN2_22") (pintype "bidirectional"))
    )
    (net (code "58") (name "MOTOR_A_OUT1") (class "Default")
      (node (ref "IC7") (pin "1") (pinfunction "A01_1") (pintype "bidirectional"))
      (node (ref "IC7") (pin "2") (pinfunction "A01_2") (pintype "bidirectional"))
      (node (ref "X12") (pin "4") (pinfunction "1_4") (pintype "passive"))
    )
    (net (code "59") (name "MOTOR_A_OUT2") (class "Default")
      (node (ref "IC7") (pin "5") (pinfunction "A02_5") (pintype "bidirectional"))
      (node (ref "IC7") (pin "6") (pinfunction "A02_6") (pintype "bidirectional"))
      (node (ref "X12") (pin "3") (pinfunction "1_3") (pintype "passive"))
    )
    (net (code "60") (name "MOTOR_A_PWM") (class "Default")
      (node (ref "IC5") (pin "19") (pinfunction "PC3_19") (pintype "bidirectional"))
      (node (ref "IC7") (pin "23") (pinfunction "PWMA_23") (pintype "bidirectional"))
    )
    (net (code "61") (name "MOTOR_B_IN1") (class "Default")
      (node (ref "IC5") (pin "42") (pinfunction "PE6_42") (pintype "bidirectional"))
      (node (ref "IC7") (pin "17") (pinfunction "BIN1_17") (pintype "bidirectional"))
    )
    (net (code "62") (name "MOTOR_B_IN2") (class "Default")
      (node (ref "IC5") (pin "43") (pinfunction "PE7_43") (pintype "bidirectional"))
      (node (ref "IC7") (pin "16") (pinfunction "BIN2_16") (pintype "bidirectional"))
    )
    (net (code "63") (name "MOTOR_B_OUT1") (class "Default")
      (node (ref "IC7") (pin "11") (pinfunction "B01_11") (pintype "bidirectional"))
      (node (ref "IC7") (pin "12") (pinfunction "B01_12") (pintype "bidirectional"))
      (node (ref "X12") (pin "1") (pinfunction "1_1") (pintype "passive"))
    )
    (net (code "64") (name "MOTOR_B_OUT2") (class "Default")
      (node (ref "IC7") (pin "7") (pinfunction "B02_7") (pintype "bidirectional"))
      (node (ref "IC7") (pin "8") (pinfunction "B02_8") (pintype "bidirectional"))
      (node (ref "X12") (pin "2") (pinfunction "1_2") (pintype "passive"))
    )
    (net (code "65") (name "MOTOR_B_PWM") (class "Default")
      (node (ref "IC5") (pin "18") (pinfunction "PC2_18") (pintype "bidirectional"))
      (node (ref "IC7") (pin "15") (pinfunction "PWMB_15") (pintype "bidirectional"))
    )
    (net (code "66") (name "MOTOR_STBY") (class "Default")
      (node (ref "IC5") (pin "4") (pinfunction "PA6_4") (pintype "bidirectional"))
      (node (ref "IC7") (pin "19") (pinfunction "STBY_19") (pintype "bidirectional"))
    )
    (net (code "67") (name "Net-(C11-Pad1)") (class "Default")
      (node (ref "C11") (pin "1") (pinfunction "1_1") (pintype "passive"))
      (node (ref "R18") (pin "2") (pinfunction "2_2") (pintype "passive"))
    )
    (net (code "68") (name "Net-(D1-PadLED_A)") (class "Default")
      (node (ref "D1") (pin "LED_A") (pinfunction "LED_A_LED_A") (pintype "bidirectional"))
      (node (ref "R25") (pin "1") (pinfunction "1_1") (pintype "passive"))
    )
    (net (code "69") (name "Net-(D2-PadLED_A)") (class "Default")
      (node (ref "D2") (pin "LED_A") (pinfunction "LED_A_LED_A") (pintype "bidirectional"))
      (node (ref "R26") (pin "1") (pinfunction "1_1") (pintype "passive"))
    )
    (net (code "70") (name "Net-(D3-PadLED_A)") (class "Default")
      (node (ref "D3") (pin "LED_A") (pinfunction "LED_A_LED_A") (pintype "bidirectional"))
      (node (ref "R31") (pin "1") (pinfunction "1_1") (pintype "passive"))
    )
    (net (code "71") (name "Net-(D4-PadLED_A)") (class "Default")
      (node (ref "D4") (pin "LED_A") (pinfunction "LED_A_LED_A") (pintype "bidirectional"))
      (node (ref "R32") (pin "1") (pinfunction "1_1") (pintype "passive"))
    )
    (net (code "72") (name "Net-(IC1-Y0)") (class "Default")
      (node (ref "IC1") (pin "15") (pinfunction "Y0_15") (pintype "output"))
      (node (ref "IC3") (pin "1") (pinfunction "I1_1") (pintype "input"))
    )
    (net (code "73") (name "Net-(IC1-Y1)") (class "Default")
      (node (ref "IC1") (pin "14") (pinfunction "Y1_14") (pintype "output"))
      (node (ref "IC3") (pin "2") (pinfunction "I2_2") (pintype "input"))
    )
    (net (code "74") (name "Net-(IC1-Y2)") (class "Default")
      (node (ref "IC1") (pin "13") (pinfunction "Y2_13") (pintype "output"))
      (node (ref "IC3") (pin "3") (pinfunction "I3_3") (pintype "input"))
    )
    (net (code "75") (name "Net-(IC1-Y3)") (class "Default")
      (node (ref "IC1") (pin "12") (pinfunction "Y3_12") (pintype "output"))
      (node (ref "IC3") (pin "4") (pinfunction "I4_4") (pintype "input"))
    )
    (net (code "76") (name "Net-(IC1-Y4)") (class "Default")
      (node (ref "IC1") (pin "11") (pinfunction "Y4_11") (pintype "output"))
      (node (ref "IC3") (pin "5") (pinfunction "I5_5") (pintype "input"))
    )
    (net (code "77") (name "Net-(IC1-Y5)") (class "Default")
      (node (ref "IC1") (pin "10") (pinfunction "Y5_10") (pintype "output"))
      (node (ref "IC3") (pin "6") (pinfunction "I6_6") (pintype "input"))
    )
    (net (code "78") (name "Net-(IC1-Y6)") (class "Default")
      (node (ref "IC1") (pin "9") (pinfunction "Y6_9") (pintype "output"))
      (node (ref "IC3") (pin "7") (pinfunction "I7_7") (pintype "input"))
    )
    (net (code "79") (name "Net-(IC1-Y7)") (class "Default")
      (node (ref "IC1") (pin "7") (pinfunction "Y7_7") (pintype "output"))
      (node (ref "IC3") (pin "8") (pinfunction "I8_8") (pintype "input"))
    )
    (net (code "80") (name "Net-(IC2-Y0)") (class "Default")
      (node (ref "IC2") (pin "15") (pinfunction "Y0_15") (pintype "output"))
      (node (ref "IC4") (pin "1") (pinfunction "I1_1") (pintype "input"))
    )
    (net (code "81") (name "Net-(IC2-Y1)") (class "Default")
      (node (ref "IC2") (pin "14") (pinfunction "Y1_14") (pintype "output"))
      (node (ref "IC4") (pin "2") (pinfunction "I2_2") (pintype "input"))
    )
    (net (code "82") (name "Net-(IC2-Y2)") (class "Default")
      (node (ref "IC2") (pin "13") (pinfunction "Y2_13") (pintype "output"))
      (node (ref "IC4") (pin "3") (pinfunction "I3_3") (pintype "input"))
    )
    (net (code "83") (name "Net-(IC2-Y3)") (class "Default")
      (node (ref "IC2") (pin "12") (pinfunction "Y3_12") (pintype "output"))
      (node (ref "IC4") (pin "4") (pinfunction "I4_4") (pintype "input"))
    )
    (net (code "84") (name "Net-(IC2-Y4)") (class "Default")
      (node (ref "IC2") (pin "11") (pinfunction "Y4_11") (pintype "output"))
      (node (ref "IC4") (pin "5") (pinfunction "I5_5") (pintype "input"))
    )
    (net (code "85") (name "Net-(IC2-Y5)") (class "Default")
      (node (ref "IC2") (pin "10") (pinfunction "Y5_10") (pintype "output"))
      (node (ref "IC4") (pin "6") (pinfunction "I6_6") (pintype "input"))
    )
    (net (code "86") (name "Net-(IC2-Y6)") (class "Default")
      (node (ref "IC2") (pin "9") (pinfunction "Y6_9") (pintype "output"))
      (node (ref "IC4") (pin "7") (pinfunction "I7_7") (pintype "input"))
    )
    (net (code "87") (name "Net-(IC2-Y7)") (class "Default")
      (node (ref "IC2") (pin "7") (pinfunction "Y7_7") (pintype "output"))
      (node (ref "IC4") (pin "8") (pinfunction "I8_8") (pintype "input"))
    )
    (net (code "88") (name "Net-(IC5-PA0)") (class "Default")
      (node (ref "IC5") (pin "62") (pinfunction "PA0_62") (pintype "bidirectional"))
      (node (ref "R8") (pin "2") (pinfunction "2_2") (pintype "passive"))
      (node (ref "R9") (pin "1") (pinfunction "1_1") (pintype "passive"))
    )
    (net (code "89") (name "Net-(IC5-PR0)") (class "Default")
      (node (ref "C7") (pin "2") (pinfunction "2_2") (pintype "passive"))
      (node (ref "IC5") (pin "58") (pinfunction "PR0_58") (pintype "bidirectional"))
      (node (ref "Q4") (pin "2") (pinfunction "2_2") (pintype "passive"))
    )
    (net (code "90") (name "Net-(IC5-PR1)") (class "Default")
      (node (ref "C8") (pin "2") (pinfunction "2_2") (pintype "passive"))
      (node (ref "IC5") (pin "59") (pinfunction "PR1_59") (pintype "bidirectional"))
      (node (ref "Q4") (pin "1") (pinfunction "1_1") (pintype "passive"))
    )
    (net (code "91") (name "Net-(IC8-FC2)") (class "Default")
      (node (ref "C12") (pin "1") (pinfunction "1_1") (pintype "passive"))
      (node (ref "IC8") (pin "2") (pinfunction "FC2_2") (pintype "bidirectional"))
    )
    (net (code "92") (name "Net-(IC8-VIN)") (class "Default")
      (node (ref "IC8") (pin "4") (pinfunction "VIN_4") (pintype "bidirectional"))
      (node (ref "R18") (pin "1") (pinfunction "1_1") (pintype "passive"))
      (node (ref "R19") (pin "2") (pinfunction "2_2") (pintype "passive"))
    )
    (net (code "93") (name "Net-(LED1-PadA)") (class "Default")
      (node (ref "LED1") (pin "A") (pinfunction "A_A") (pintype "passive"))
      (node (ref "R13") (pin "2") (pinfunction "2_2") (pintype "passive"))
    )
    (net (code "94") (name "Net-(LED2-PadA)") (class "Default")
      (node (ref "LED2") (pin "A") (pinfunction "A_A") (pintype "passive"))
      (node (ref "R14") (pin "2") (pinfunction "2_2") (pintype "passive"))
    )
    (net (code "95") (name "Net-(LED3-PadC)") (class "Default")
      (node (ref "LED3") (pin "C") (pinfunction "C_C") (pintype "passive"))
      (node (ref "R20") (pin "1") (pinfunction "1_1") (pintype "passive"))
    )
    (net (code "96") (name "Net-(Q1-PadG)") (class "Default")
      (node (ref "Q1") (pin "G") (pinfunction "G_G") (pintype "passive"))
      (node (ref "R1") (pin "2") (pinfunction "2_2") (pintype "passive"))
    )
    (net (code "97") (name "Net-(Q1-PadS)") (class "Default")
      (node (ref "Q1") (pin "S") (pinfunction "S_S") (pintype "passive"))
      (node (ref "R6") (pin "1") (pinfunction "1_1") (pintype "passive"))
    )
    (net (code "98") (name "Net-(Q2-PadG)") (class "Default")
      (node (ref "Q2") (pin "G") (pinfunction "G_G") (pintype "passive"))
      (node (ref "R2") (pin "2") (pinfunction "2_2") (pintype "passive"))
    )
    (net (code "99") (name "Net-(Q2-PadS)") (class "Default")
      (node (ref "Q2") (pin "S") (pinfunction "S_S") (pintype "passive"))
      (node (ref "R5") (pin "1") (pinfunction "1_1") (pintype "passive"))
    )
    (net (code "100") (name "Net-(Q3-PadG)") (class "Default")
      (node (ref "Q3") (pin "G") (pinfunction "G_G") (pintype "passive"))
      (node (ref "R3") (pin "2") (pinfunction "2_2") (pintype "passive"))
    )
    (net (code "101") (name "Net-(Q3-PadS)") (class "Default")
      (node (ref "Q3") (pin "S") (pinfunction "S_S") (pintype "passive"))
      (node (ref "R4") (pin "1") (pinfunction "1_1") (pintype "passive"))
    )
    (net (code "102") (name "Net-(Q5-PadG)") (class "Default")
      (node (ref "Q5") (pin "G") (pinfunction "G_G") (pintype "passive"))
      (node (ref "R11") (pin "2") (pinfunction "2_2") (pintype "passive"))
    )
    (net (code "103") (name "Net-(Q6-PadG)") (class "Default")
      (node (ref "Q6") (pin "G") (pinfunction "G_G") (pintype "passive"))
      (node (ref "R15") (pin "2") (pinfunction "2_2") (pintype "passive"))
    )
    (net (code "104") (name "Net-(Q7-G2)") (class "Default")
      (node (ref "Q7") (pin "4") (pinfunction "G2_4") (pintype "passive"))
      (node (ref "Q7") (pin "7") (pinfunction "D1_7") (pintype "bidirectional"))
      (node (ref "Q7") (pin "8") (pinfunction "D1_8") (pintype "bidirectional"))
      (node (ref "R23") (pin "2") (pinfunction "2_2") (pintype "passive"))
      (node (ref "R24") (pin "1") (pinfunction "1_1") (pintype "passive"))
    )
    (net (code "105") (name "Net-(S1-P)") (class "Default")
      (node (ref "C17") (pin "1") (pinfunction "1_1") (pintype "passive"))
      (node (ref "R24") (pin "2") (pinfunction "2_2") (pintype "passive"))
      (node (ref "S1") (pin "3") (pinfunction "P_3") (pintype "passive"))
      (node (ref "S1") (pin "4") (pinfunction "P1_4") (pintype "passive"))
    )
    (net (code "106") (name "Net-(X11J-1)") (class "Default")
      (node (ref "Q5") (pin "S") (pinfunction "S_S") (pintype "passive"))
      (node (ref "X11") (pin "9") (pinfunction "1_9") (pintype "passive"))
    )
    (net (code "107") (name "PDI_CLK") (class "Default")
      (node (ref "IC5") (pin "57") (pinfunction "~{RESET}/PDI_57") (pintype "bidirectional"))
      (node (ref "R7") (pin "2") (pinfunction "2_2") (pintype "passive"))
      (node (ref "X5") (pin "5") (pinfunction "1_5") (pintype "passive"))
    )
    (net (code "108") (name "PDI_DATA") (class "Default")
      (node (ref "IC5") (pin "56") (pinfunction "PDI_56") (pintype "bidirectional"))
      (node (ref "X5") (pin "1") (pinfunction "1_1") (pintype "passive"))
    )
    (net (code "109") (name "POWER_OFF") (class "Default")
      (node (ref "IC5") (pin "5") (pinfunction "PA7_5") (pintype "bidirectional"))
      (node (ref "Q7") (pin "2") (pinfunction "G1_2") (pintype "passive"))
      (node (ref "R30") (pin "2") (pinfunction "2_2") (pintype "passive"))
      (node (ref "S1") (pin "1") (pinfunction "S_1") (pintype "passive"))
      (node (ref "S1") (pin "2") (pinfunction "S1_2") (pintype "passive"))
    )
    (net (code "110") (name "RGB_LED_MK0") (class "Default")
      (node (ref "IC1") (pin "1") (pinfunction "A_1") (pintype "input"))
      (node (ref "IC5") (pin "51") (pinfunction "PF5_51") (pintype "bidirectional"))
    )
    (net (code "111") (name "RGB_LED_MK1") (class "Default")
      (node (ref "IC1") (pin "2") (pinfunction "B_2") (pintype "input"))
      (node (ref "IC5") (pin "50") (pinfunction "PF4_50") (pintype "bidirectional"))
    )
    (net (code "112") (name "RGB_LED_MK2") (class "Default")
      (node (ref "IC1") (pin "3") (pinfunction "C_3") (pintype "input"))
      (node (ref "IC5") (pin "49") (pinfunction "PF3_49") (pintype "bidirectional"))
    )
    (net (code "113") (name "RPI_RX") (class "Default")
      (node (ref "IC5") (pin "29") (pinfunction "PD3_29") (pintype "bidirectional"))
      (node (ref "IC9") (pin "GPIO_15") (pinfunction "GPIO_15_GPIO_15") (pintype "bidirectional"))
    )
    (net (code "114") (name "RPI_TX") (class "Default")
      (node (ref "IC5") (pin "28") (pinfunction "PD2_28") (pintype "bidirectional"))
      (node (ref "IC9") (pin "GPIO_14") (pinfunction "GPIO_14_GPIO_14") (pintype "bidirectional"))
    )
    (net (code "115") (name "SCL") (class "Default")
      (node (ref "IC5") (pin "17") (pinfunction "PC1_17") (pintype "bidirectional"))
      (node (ref "IC6") (pin "SCL") (pinfunction "SCL_SCL") (pintype "bidirectional"))
      (node (ref "IC9") (pin "GPIO_1") (pinfunction "GPIO_1_GPIO_1") (pintype "bidirectional"))
      (node (ref "R12") (pin "2") (pinfunction "2_2") (pintype "passive"))
      (node (ref "X10") (pin "3") (pinfunction "1_3") (pintype "passive"))
    )
    (net (code "116") (name "SDA") (class "Default")
      (node (ref "IC5") (pin "16") (pinfunction "PC0_16") (pintype "bidirectional"))
      (node (ref "IC6") (pin "SDA") (pinfunction "SDA_SDA") (pintype "bidirectional"))
      (node (ref "IC9") (pin "GPIO_0") (pinfunction "GPIO_0_GPIO_0") (pintype "bidirectional"))
      (node (ref "R10") (pin "2") (pinfunction "2_2") (pintype "passive"))
      (node (ref "X10") (pin "4") (pinfunction "1_4") (pintype "passive"))
    )
    (net (code "117") (name "SPEAKER_O1") (class "Default")
      (node (ref "IC8") (pin "8") (pinfunction "VO2_8") (pintype "bidirectional"))
      (node (ref "X13") (pin "2") (pinfunction "1_2") (pintype "passive"))
    )
    (net (code "118") (name "SPEAKER_O2") (class "Default")
      (node (ref "IC8") (pin "5") (pinfunction "VO1_5") (pintype "bidirectional"))
      (node (ref "R19") (pin "1") (pinfunction "1_1") (pintype "passive"))
      (node (ref "X13") (pin "3") (pinfunction "1_3") (pintype "passive"))
    )
    (net (code "119") (name "unconnected-(IC3-CD+-Pad10)") (class "Default")
      (node (ref "IC3") (pin "10") (pinfunction "CD+_10") (pintype "passive"))
    )
    (net (code "120") (name "unconnected-(IC4-CD+-Pad10)") (class "Default")
      (node (ref "IC4") (pin "10") (pinfunction "CD+_10") (pintype "passive"))
    )
    (net (code "121") (name "unconnected-(IC5-PA5-Pad3)") (class "Default")
      (node (ref "IC5") (pin "3") (pinfunction "PA5_3") (pintype "bidirectional"))
    )
    (net (code "122") (name "unconnected-(IC5-PF7-Pad55)") (class "Default")
      (node (ref "IC5") (pin "55") (pinfunction "PF7_55") (pintype "bidirectional"))
    )
    (net (code "123") (name "unconnected-(IC6-PadA_INT1)") (class "Default")
      (node (ref "IC6") (pin "A_INT1") (pinfunction "A_INT1_A_INT1") (pintype "bidirectional"))
    )
    (net (code "124") (name "unconnected-(IC6-PadG_INT)") (class "Default")
      (node (ref "IC6") (pin "G_INT") (pinfunction "G_INT_G_INT") (pintype "bidirectional"))
    )
    (net (code "125") (name "unconnected-(IC6-PadM_DRDY)") (class "Default")
      (node (ref "IC6") (pin "M_DRDY") (pinfunction "M_DRDY_M_DRDY") (pintype "bidirectional"))
    )
    (net (code "126") (name "unconnected-(IC6-PadP_E0C)") (class "Default")
      (node (ref "IC6") (pin "P_E0C") (pinfunction "P_E0C_P_E0C") (pintype "bidirectional"))
    )
    (net (code "127") (name "unconnected-(IC6-PadP_XCLR)") (class "Default")
      (node (ref "IC6") (pin "P_XCLR") (pinfunction "P_XCLR_P_XCLR") (pintype "bidirectional"))
    )
    (net (code "128") (name "unconnected-(IC8-FC1-Pad3)") (class "Default")
      (node (ref "IC8") (pin "3") (pinfunction "FC1_3") (pintype "bidirectional"))
    )
    (net (code "129") (name "unconnected-(IC9-PadGPIO_4)") (class "Default")
      (node (ref "IC9") (pin "GPIO_4") (pinfunction "GPIO_4_GPIO_4") (pintype "bidirectional"))
    )
    (net (code "130") (name "unconnected-(IC9-PadGPIO_7)") (class "Default")
      (node (ref "IC9") (pin "GPIO_7") (pinfunction "GPIO_7_GPIO_7") (pintype "bidirectional"))
    )
    (net (code "131") (name "unconnected-(IC9-PadGPIO_8)") (class "Default")
      (node (ref "IC9") (pin "GPIO_8") (pinfunction "GPIO_8_GPIO_8") (pintype "bidirectional"))
    )
    (net (code "132") (name "unconnected-(IC9-PadGPIO_9)") (class "Default")
      (node (ref "IC9") (pin "GPIO_9") (pinfunction "GPIO_9_GPIO_9") (pintype "bidirectional"))
    )
    (net (code "133") (name "unconnected-(IC9-PadGPIO_10)") (class "Default")
      (node (ref "IC9") (pin "GPIO_10") (pinfunction "GPIO_10_GPIO_10") (pintype "bidirectional"))
    )
    (net (code "134") (name "unconnected-(IC9-PadGPIO_11)") (class "Default")
      (node (ref "IC9") (pin "GPIO_11") (pinfunction "GPIO_11_GPIO_11") (pintype "bidirectional"))
    )
    (net (code "135") (name "unconnected-(IC9-PadGPIO_17)") (class "Default")
      (node (ref "IC9") (pin "GPIO_17") (pinfunction "GPIO_17_GPIO_17") (pintype "bidirectional"))
    )
    (net (code "136") (name "unconnected-(IC9-PadGPIO_18)") (class "Default")
      (node (ref "IC9") (pin "GPIO_18") (pinfunction "GPIO_18_GPIO_18") (pintype "bidirectional"))
    )
    (net (code "137") (name "unconnected-(IC9-PadGPIO_21)") (class "Default")
      (node (ref "IC9") (pin "GPIO_21") (pinfunction "GPIO_21_GPIO_21") (pintype "bidirectional"))
    )
    (net (code "138") (name "unconnected-(IC9-PadGPIO_22)") (class "Default")
      (node (ref "IC9") (pin "GPIO_22") (pinfunction "GPIO_22_GPIO_22") (pintype "bidirectional"))
    )
    (net (code "139") (name "unconnected-(IC9-PadGPIO_23)") (class "Default")
      (node (ref "IC9") (pin "GPIO_23") (pinfunction "GPIO_23_GPIO_23") (pintype "bidirectional"))
    )
    (net (code "140") (name "unconnected-(IC9-PadGPIO_24)") (class "Default")
      (node (ref "IC9") (pin "GPIO_24") (pinfunction "GPIO_24_GPIO_24") (pintype "bidirectional"))
    )
    (net (code "141") (name "unconnected-(IC9-PadGPIO_25)") (class "Default")
      (node (ref "IC9") (pin "GPIO_25") (pinfunction "GPIO_25_GPIO_25") (pintype "bidirectional"))
    )
    (net (code "142") (name "unconnected-(X5C-1-Pad3)") (class "Default")
      (node (ref "X5") (pin "3") (pinfunction "1_3") (pintype "passive"))
    )
    (net (code "143") (name "unconnected-(X5D-1-Pad4)") (class "Default")
      (node (ref "X5") (pin "4") (pinfunction "1_4") (pintype "passive"))
    )
    (net (code "144") (name "unconnected-(X10F-1-Pad6)") (class "Default")
      (node (ref "X10") (pin "6") (pinfunction "1_6") (pintype "passive"))
    )
    (net (code "145") (name "unconnected-(X11-Pad1)") (class "Default")
      (node (ref "X11") (pin "1") (pinfunction "1_1") (pintype "passive"))
    )
  )
)
